# Sheet1.net
KiCad netlist of a schematic drawn in Altium Designer
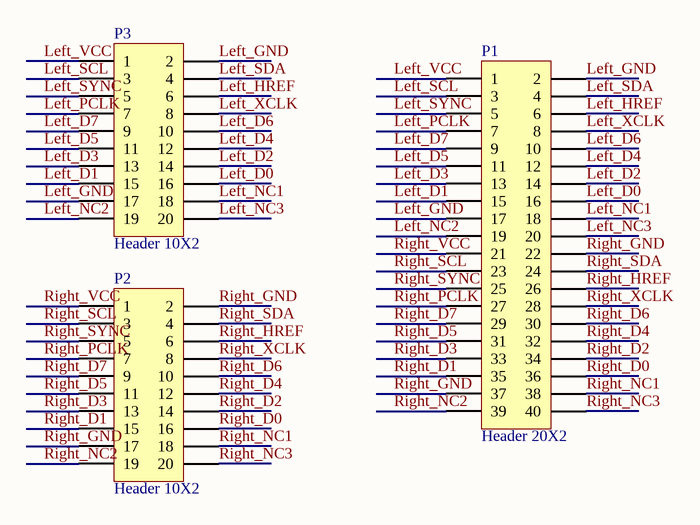
[diagram p0: Sheet1.SchDoc]

(export (version "E")
  (design (tool "Eeschema 10.0.6"))
  (components
    (comp (ref "P1")
      (value "Header 20X2")
      (footprint "FPC_40pin_05mm")
      (description "Header, 20-Pin, Dual row")
      (fields (field (name "PUBLISHER") "Altium Limited"))
      (libsource (lib "Miscellaneous Connectors") (part "Header 20X2"))
    )
    (comp (ref "P2")
      (value "Header 10X2")
      (footprint "HDR2X10")
      (description "Header, 10-Pin, Dual row")
      (fields (field (name "PUBLISHER") "Altium Limited"))
      (libsource (lib "Miscellaneous Connectors") (part "Header 10X2"))
    )
    (comp (ref "P3")
      (value "Header 10X2")
      (footprint "HDR2X10")
      (description "Header, 10-Pin, Dual row")
      (fields (field (name "PUBLISHER") "Altium Limited"))
      (libsource (lib "Miscellaneous Connectors") (part "Header 10X2"))
    )
  )
  (nets
    (net (code "1") (name "/Left_D0") (class "Default")
      (node (ref "P1") (pin "16") (pinfunction "16_16") (pintype "passive"))
      (node (ref "P3") (pin "16") (pinfunction "16_16") (pintype "passive"))
    )
    (net (code "2") (name "/Left_D1") (class "Default")
      (node (ref "P1") (pin "15") (pinfunction "15_15") (pintype "passive"))
      (node (ref "P3") (pin "15") (pinfunction "15_15") (pintype "passive"))
    )
    (net (code "3") (name "/Left_D2") (class "Default")
      (node (ref "P1") (pin "14") (pinfunction "14_14") (pintype "passive"))
      (node (ref "P3") (pin "14") (pinfunction "14_14") (pintype "passive"))
    )
    (net (code "4") (name "/Left_D3") (class "Default")
      (node (ref "P1") (pin "13") (pinfunction "13_13") (pintype "passive"))
      (node (ref "P3") (pin "13") (pinfunction "13_13") (pintype "passive"))
    )
    (net (code "5") (name "/Left_D4") (class "Default")
      (node (ref "P1") (pin "12") (pinfunction "12_12") (pintype "passive"))
      (node (ref "P3") (pin "12") (pinfunction "12_12") (pintype "passive"))
    )
    (net (code "6") (name "/Left_D5") (class "Default")
      (node (ref "P1") (pin "11") (pinfunction "11_11") (pintype "passive"))
      (node (ref "P3") (pin "11") (pinfunction "11_11") (pintype "passive"))
    )
    (net (code "7") (name "/Left_D6") (class "Default")
      (node (ref "P1") (pin "10") (pinfunction "10_10") (pintype "passive"))
      (node (ref "P3") (pin "10") (pinfunction "10_10") (pintype "passive"))
    )
    (net (code "8") (name "/Left_D7") (class "Default")
      (node (ref "P1") (pin "9") (pinfunction "9_9") (pintype "passive"))
      (node (ref "P3") (pin "9") (pinfunction "9_9") (pintype "passive"))
    )
    (net (code "9") (name "/Left_GND") (class "Default")
      (node (ref "P1") (pin "17") (pinfunction "17_17") (pintype "passive"))
      (node (ref "P1") (pin "2") (pinfunction "2_2") (pintype "passive"))
      (node (ref "P3") (pin "17") (pinfunction "17_17") (pintype "passive"))
      (node (ref "P3") (pin "2") (pinfunction "2_2") (pintype "passive"))
    )
    (net (code "10") (name "/Left_HREF") (class "Default")
      (node (ref "P1") (pin "6") (pinfunction "6_6") (pintype "passive"))
      (node (ref "P3") (pin "6") (pinfunction "6_6") (pintype "passive"))
    )
    (net (code "11") (name "/Left_NC1") (class "Default")
      (node (ref "P1") (pin "18") (pinfunction "18_18") (pintype "passive"))
      (node (ref "P3") (pin "18") (pinfunction "18_18") (pintype "passive"))
    )
    (net (code "12") (name "/Left_NC2") (class "Default")
      (node (ref "P1") (pin "19") (pinfunction "19_19") (pintype "passive"))
      (node (ref "P3") (pin "19") (pinfunction "19_19") (pintype "passive"))
    )
    (net (code "13") (name "/Left_NC3") (class "Default")
      (node (ref "P1") (pin "20") (pinfunction "20_20") (pintype "passive"))
      (node (ref "P3") (pin "20") (pinfunction "20_20") (pintype "passive"))
    )
    (net (code "14") (name "/Left_PCLK") (class "Default")
      (node (ref "P1") (pin "7") (pinfunction "7_7") (pintype "passive"))
      (node (ref "P3") (pin "7") (pinfunction "7_7") (pintype "passive"))
    )
    (net (code "15") (name "/Left_SCL") (class "Default")
      (node (ref "P1") (pin "3") (pinfunction "3_3") (pintype "passive"))
      (node (ref "P3") (pin "3") (pinfunction "3_3") (pintype "passive"))
    )
    (net (code "16") (name "/Left_SDA") (class "Default")
      (node (ref "P1") (pin "4") (pinfunction "4_4") (pintype "passive"))
      (node (ref "P3") (pin "4") (pinfunction "4_4") (pintype "passive"))
    )
    (net (code "17") (name "/Left_SYNC") (class "Default")
      (node (ref "P1") (pin "5") (pinfunction "5_5") (pintype "passive"))
      (node (ref "P3") (pin "5") (pinfunction "5_5") (pintype "passive"))
    )
    (net (code "18") (name "/Left_VCC") (class "Default")
      (node (ref "P1") (pin "1") (pinfunction "1_1") (pintype "passive"))
      (node (ref "P3") (pin "1") (pinfunction "1_1") (pintype "passive"))
    )
    (net (code "19") (name "/Left_XCLK") (class "Default")
      (node (ref "P1") (pin "8") (pinfunction "8_8") (pintype "passive"))
      (node (ref "P3") (pin "8") (pinfunction "8_8") (pintype "passive"))
    )
    (net (code "20") (name "/Right_D0") (class "Default")
      (node (ref "P1") (pin "36") (pinfunction "36_36") (pintype "passive"))
      (node (ref "P2") (pin "16") (pinfunction "16_16") (pintype "passive"))
    )
    (net (code "21") (name "/Right_D1") (class "Default")
      (node (ref "P1") (pin "35") (pinfunction "35_35") (pintype "passive"))
      (node (ref "P2") (pin "15") (pinfunction "15_15") (pintype "passive"))
    )
    (net (code "22") (name "/Right_D2") (class "Default")
      (node (ref "P1") (pin "34") (pinfunction "34_34") (pintype "passive"))
      (node (ref "P2") (pin "14") (pinfunction "14_14") (pintype "passive"))
    )
    (net (code "23") (name "/Right_D3") (class "Default")
      (node (ref "P1") (pin "33") (pinfunction "33_33") (pintype "passive"))
      (node (ref "P2") (pin "13") (pinfunction "13_13") (pintype "passive"))
    )
    (net (code "24") (name "/Right_D4") (class "Default")
      (node (ref "P1") (pin "32") (pinfunction "32_32") (pintype "passive"))
      (node (ref "P2") (pin "12") (pinfunction "12_12") (pintype "passive"))
    )
    (net (code "25") (name "/Right_D5") (class "Default")
      (node (ref "P1") (pin "31") (pinfunction "31_31") (pintype "passive"))
      (node (ref "P2") (pin "11") (pinfunction "11_11") (pintype "passive"))
    )
    (net (code "26") (name "/Right_D6") (class "Default")
      (node (ref "P1") (pin "30") (pinfunction "30_30") (pintype "passive"))
      (node (ref "P2") (pin "10") (pinfunction "10_10") (pintype "passive"))
    )
    (net (code "27") (name "/Right_D7") (class "Default")
      (node (ref "P1") (pin "29") (pinfunction "29_29") (pintype "passive"))
      (node (ref "P2") (pin "9") (pinfunction "9_9") (pintype "passive"))
    )
    (net (code "28") (name "/Right_GND") (class "Default")
      (node (ref "P1") (pin "22") (pinfunction "22_22") (pintype "passive"))
      (node (ref "P1") (pin "37") (pinfunction "37_37") (pintype "passive"))
      (node (ref "P2") (pin "17") (pinfunction "17_17") (pintype "passive"))
      (node (ref "P2") (pin "2") (pinfunction "2_2") (pintype "passive"))
    )
    (net (code "29") (name "/Right_HREF") (class "Default")
      (node (ref "P1") (pin "26") (pinfunction "26_26") (pintype "passive"))
      (node (ref "P2") (pin "6") (pinfunction "6_6") (pintype "passive"))
    )
    (net (code "30") (name "/Right_NC1") (class "Default")
      (node (ref "P1") (pin "38") (pinfunction "38_38") (pintype "passive"))
      (node (ref "P2") (pin "18") (pinfunction "18_18") (pintype "passive"))
    )
    (net (code "31") (name "/Right_NC2") (class "Default")
      (node (ref "P1") (pin "39") (pinfunction "39_39") (pintype "passive"))
      (node (ref "P2") (pin "19") (pinfunction "19_19") (pintype "passive"))
    )
    (net (code "32") (name "/Right_NC3") (class "Default")
      (node (ref "P1") (pin "40") (pinfunction "40_40") (pintype "passive"))
      (node (ref "P2") (pin "20") (pinfunction "20_20") (pintype "passive"))
    )
    (net (code "33") (name "/Right_PCLK") (class "Default")
      (node (ref "P1") (pin "27") (pinfunction "27_27") (pintype "passive"))
      (node (ref "P2") (pin "7") (pinfunction "7_7") (pintype "passive"))
    )
    (net (code "34") (name "/Right_SCL") (class "Default")
      (node (ref "P1") (pin "23") (pinfunction "23_23") (pintype "passive"))
      (node (ref "P2") (pin "3") (pinfunction "3_3") (pintype "passive"))
    )
    (net (code "35") (name "/Right_SDA") (class "Default")
      (node (ref "P1") (pin "24") (pinfunction "24_24") (pintype "passive"))
      (node (ref "P2") (pin "4") (pinfunction "4_4") (pintype "passive"))
    )
    (net (code "36") (name "/Right_SYNC") (class "Default")
      (node (ref "P1") (pin "25") (pinfunction "25_25") (pintype "passive"))
      (node (ref "P2") (pin "5") (pinfunction "5_5") (pintype "passive"))
    )
    (net (code "37") (name "/Right_VCC") (class "Default")
      (node (ref "P1") (pin "21") (pinfunction "21_21") (pintype "passive"))
      (node (ref "P2") (pin "1") (pinfunction "1_1") (pintype "passive"))
    )
    (net (code "38") (name "/Right_XCLK") (class "Default")
      (node (ref "P1") (pin "28") (pinfunction "28_28") (pintype "passive"))
      (node (ref "P2") (pin "8") (pinfunction "8_8") (pintype "passive"))
    )
  )
)
